# detector0.net
KiCad netlist of a schematic drawn in EAGLE
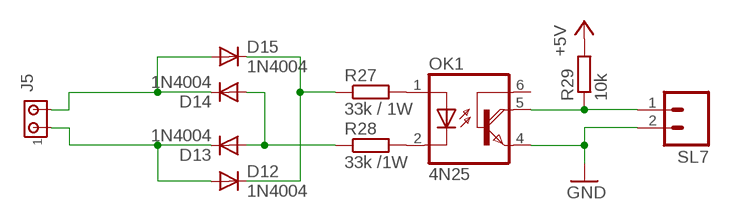
[diagram p0: schematic, sheet 1]

(export (version "E")
  (design (tool "Eeschema 10.0.6"))
  (components
    (comp (ref "D12")
      (value "1N4004")
      (footprint "eagle-import:DO41-10")
      (libsource (lib "eagle-import") (part "1N4004"))
    )
    (comp (ref "D13")
      (value "1N4004")
      (footprint "eagle-import:DO41-10")
      (libsource (lib "eagle-import") (part "1N4004"))
    )
    (comp (ref "D14")
      (value "1N4004")
      (footprint "eagle-import:DO41-10")
      (libsource (lib "eagle-import") (part "1N4004"))
    )
    (comp (ref "D15")
      (value "1N4004")
      (footprint "eagle-import:DO41-10")
      (libsource (lib "eagle-import") (part "1N4004"))
    )
    (comp (ref "J5")
      (value "MTA02-156")
      (footprint "eagle-import:1X2MTA")
      (libsource (lib "eagle-import") (part "MTA02-156"))
    )
    (comp (ref "OK1")
      (value "4N25")
      (footprint "eagle-import:DIL06")
      (fields (field (name "MF") "VISHAY/TELEFUNKEN") (field (name "MPN") "4N33"))
      (libsource (lib "eagle-import") (part "4N33"))
    )
    (comp (ref "R27")
      (value "33k / 1W")
      (footprint "eagle-import:0207_15")
      (libsource (lib "eagle-import") (part "R-EU_0207/15"))
    )
    (comp (ref "R28")
      (value "33k /1W")
      (footprint "eagle-import:0207_15")
      (libsource (lib "eagle-import") (part "R-EU_0207/15"))
    )
    (comp (ref "R29")
      (value "10k")
      (footprint "eagle-import:0207_10")
      (libsource (lib "eagle-import") (part "R-EU_0207/10"))
    )
    (comp (ref "SL7")
      (value "M02")
      (footprint "eagle-import:02P")
      (libsource (lib "eagle-import") (part "M02"))
    )
  )
  (nets
    (net (code "1") (name "+5V") (class "Default")
      (node (ref "R29") (pin "2") (pinfunction "2_2") (pintype "passive"))
    )
    (net (code "2") (name "GND") (class "Default")
      (node (ref "OK1") (pin "4") (pinfunction "E_4") (pintype "passive"))
      (node (ref "SL7") (pin "2") (pinfunction "2_2") (pintype "passive"))
    )
    (net (code "3") (name "Net-(D12-PadA)") (class "Default")
      (node (ref "D12") (pin "A") (pinfunction "A_A") (pintype "passive"))
      (node (ref "D13") (pin "C") (pinfunction "C_C") (pintype "passive"))
      (node (ref "J5") (pin "1") (pinfunction "1_1") (pintype "passive"))
    )
    (net (code "4") (name "Net-(D12-PadC)") (class "Default")
      (node (ref "D12") (pin "C") (pinfunction "C_C") (pintype "passive"))
      (node (ref "D15") (pin "C") (pinfunction "C_C") (pintype "passive"))
      (node (ref "R27") (pin "1") (pinfunction "1_1") (pintype "passive"))
    )
    (net (code "5") (name "Net-(D13-PadA)") (class "Default")
      (node (ref "D13") (pin "A") (pinfunction "A_A") (pintype "passive"))
      (node (ref "D14") (pin "A") (pinfunction "A_A") (pintype "passive"))
      (node (ref "R28") (pin "1") (pinfunction "1_1") (pintype "passive"))
    )
    (net (code "6") (name "Net-(D14-PadC)") (class "Default")
      (node (ref "D14") (pin "C") (pinfunction "C_C") (pintype "passive"))
      (node (ref "D15") (pin "A") (pinfunction "A_A") (pintype "passive"))
      (node (ref "J5") (pin "2") (pinfunction "2_2") (pintype "passive"))
    )
    (net (code "7") (name "Net-(OK1-A)") (class "Default")
      (node (ref "OK1") (pin "1") (pinfunction "A_1") (pintype "passive"))
      (node (ref "R27") (pin "2") (pinfunction "2_2") (pintype "passive"))
    )
    (net (code "8") (name "Net-(OK1-C)") (class "Default")
      (node (ref "OK1") (pin "2") (pinfunction "C_2") (pintype "passive"))
      (node (ref "R28") (pin "2") (pinfunction "2_2") (pintype "passive"))
    )
    (net (code "9") (name "Net-(OK1-COL)") (class "Default")
      (node (ref "OK1") (pin "5") (pinfunction "COL_5") (pintype "passive"))
      (node (ref "R29") (pin "1") (pinfunction "1_1") (pintype "passive"))
      (node (ref "SL7") (pin "1") (pinfunction "1_1") (pintype "passive"))
    )
    (net (code "10") (name "unconnected-(OK1-B-Pad6)") (class "Default")
      (node (ref "OK1") (pin "6") (pinfunction "B_6") (pintype "passive"))
    )
  )
)
